# dcmctrl-hb-2-board_v1.net
KiCad netlist of a schematic drawn in EAGLE
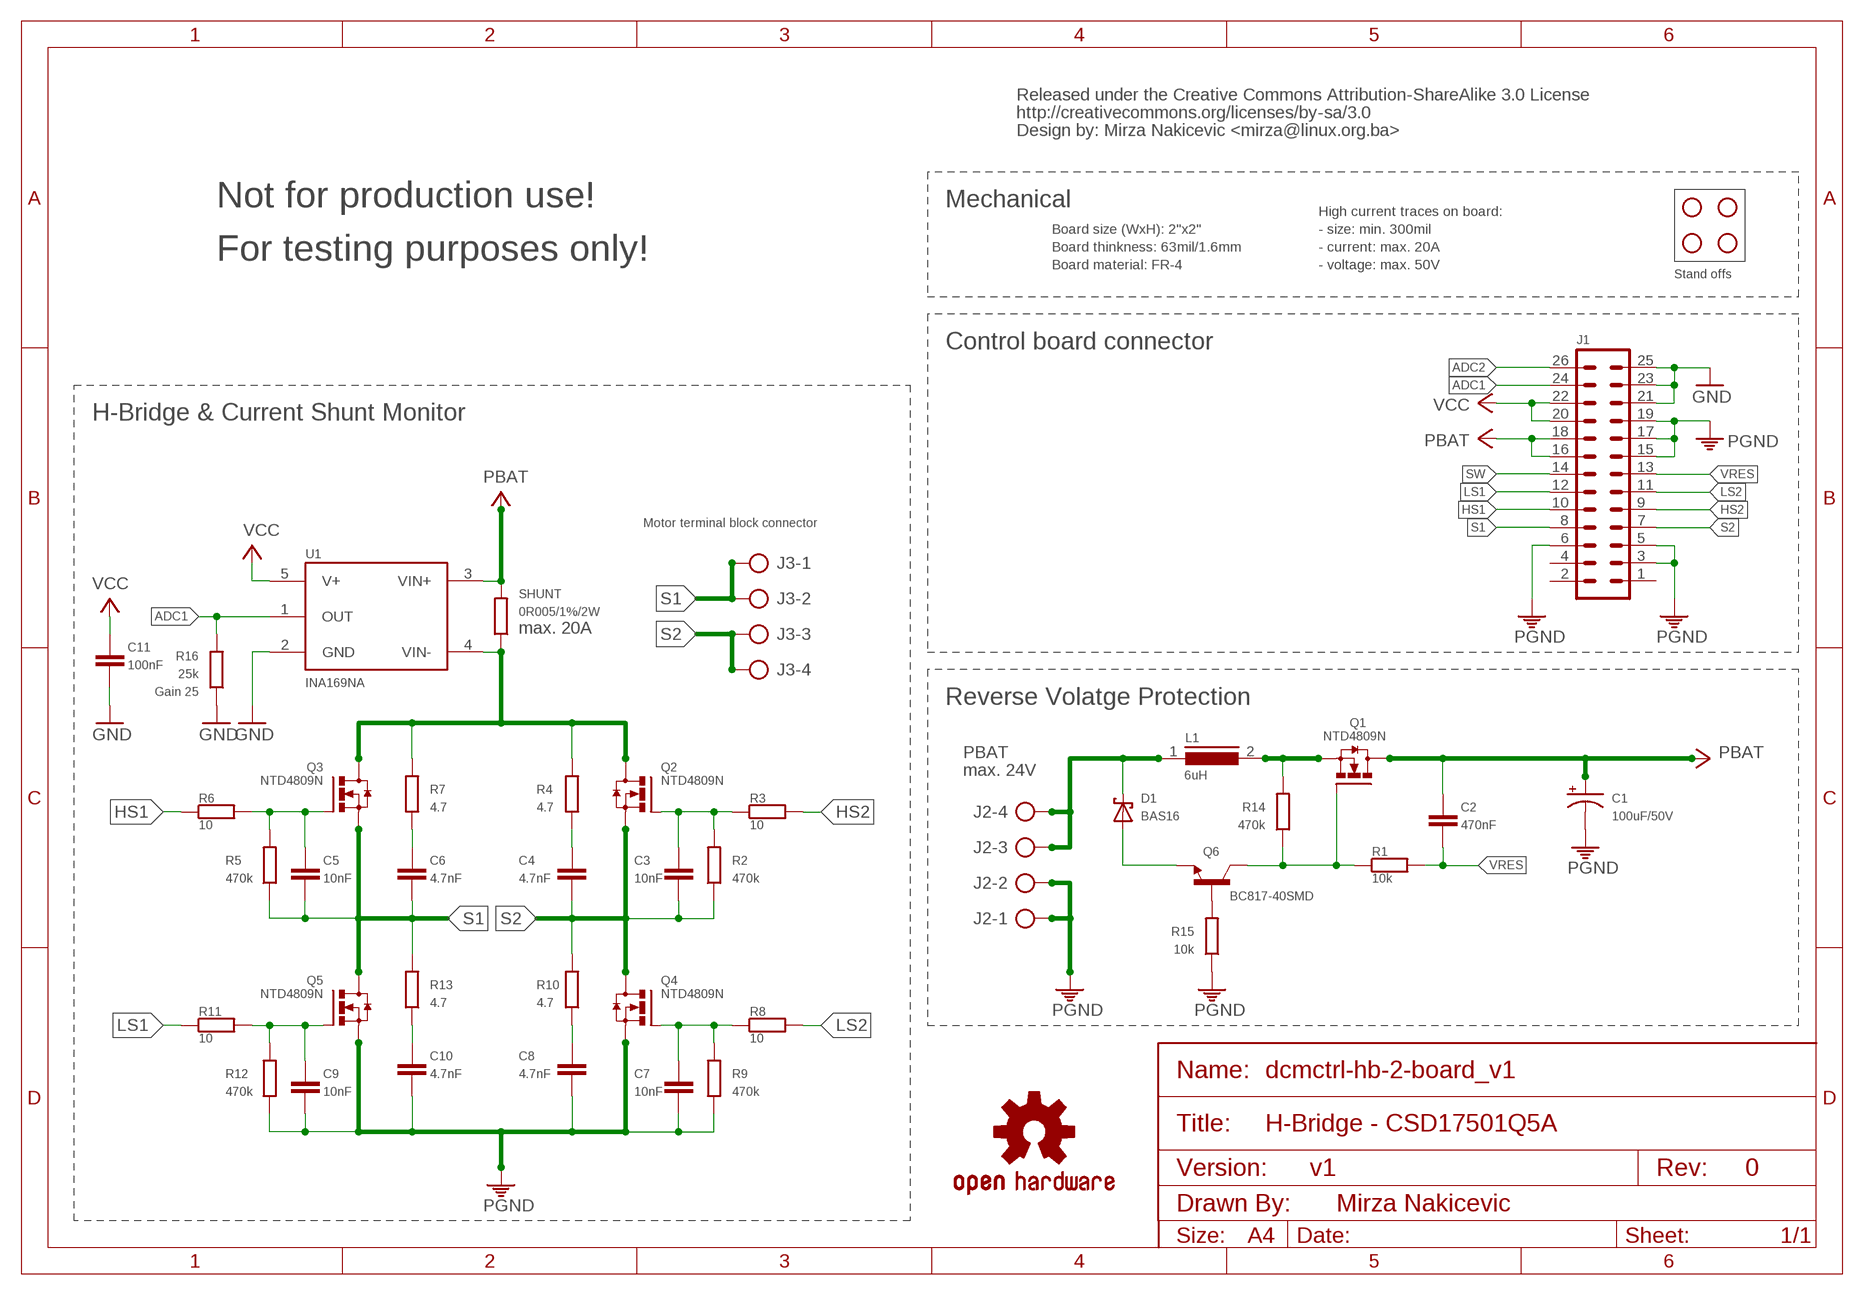
[diagram p0: schematic, sheet 1]

(export (version "E")
  (design (tool "Eeschema 10.0.6"))
  (components
    (comp (ref "C1")
      (value "100uF/50V")
      (footprint "eagle-import:E5-13")
      (libsource (lib "eagle-import") (part "CPOL-USE5-13"))
    )
    (comp (ref "C2")
      (value "470nF")
      (footprint "eagle-import:C0603")
      (libsource (lib "eagle-import") (part "C-0603"))
    )
    (comp (ref "C3")
      (value "10nF")
      (footprint "eagle-import:C0603")
      (libsource (lib "eagle-import") (part "C-0603"))
    )
    (comp (ref "C4")
      (value "4.7nF")
      (footprint "eagle-import:C0603")
      (libsource (lib "eagle-import") (part "C-0603"))
    )
    (comp (ref "C5")
      (value "10nF")
      (footprint "eagle-import:C0603")
      (libsource (lib "eagle-import") (part "C-0603"))
    )
    (comp (ref "C6")
      (value "4.7nF")
      (footprint "eagle-import:C0603")
      (libsource (lib "eagle-import") (part "C-0603"))
    )
    (comp (ref "C7")
      (value "10nF")
      (footprint "eagle-import:C0603")
      (libsource (lib "eagle-import") (part "C-0603"))
    )
    (comp (ref "C8")
      (value "4.7nF")
      (footprint "eagle-import:C0603")
      (libsource (lib "eagle-import") (part "C-0603"))
    )
    (comp (ref "C9")
      (value "10nF")
      (footprint "eagle-import:C0603")
      (libsource (lib "eagle-import") (part "C-0603"))
    )
    (comp (ref "C10")
      (value "4.7nF")
      (footprint "eagle-import:C0603")
      (libsource (lib "eagle-import") (part "C-0603"))
    )
    (comp (ref "C11")
      (value "100nF")
      (footprint "eagle-import:C0603")
      (libsource (lib "eagle-import") (part "C-0603"))
    )
    (comp (ref "D1")
      (value "BAS16")
      (footprint "eagle-import:SOT23")
      (libsource (lib "eagle-import") (part "BAS40"))
    )
    (comp (ref "J1")
      (value "MA13-2")
      (footprint "eagle-import:MA13-2")
      (libsource (lib "eagle-import") (part "MA13-2"))
    )
    (comp (ref "J2")
      (value "W237-4")
      (footprint "eagle-import:W237-4")
      (libsource (lib "eagle-import") (part "W237-4"))
    )
    (comp (ref "J3")
      (value "W237-4")
      (footprint "eagle-import:W237-4")
      (libsource (lib "eagle-import") (part "W237-4"))
    )
    (comp (ref "L1")
      (value "6uH")
      (footprint "eagle-import:DR127")
      (libsource (lib "eagle-import") (part "DR127"))
    )
    (comp (ref "Q1")
      (value "NTD4809N")
      (footprint "eagle-import:DPAK")
      (libsource (lib "eagle-import") (part "NTD4809N"))
    )
    (comp (ref "Q2")
      (value "NTD4809N")
      (footprint "eagle-import:DPAK")
      (libsource (lib "eagle-import") (part "NTD4809N"))
    )
    (comp (ref "Q3")
      (value "NTD4809N")
      (footprint "eagle-import:DPAK")
      (libsource (lib "eagle-import") (part "NTD4809N"))
    )
    (comp (ref "Q4")
      (value "NTD4809N")
      (footprint "eagle-import:DPAK")
      (libsource (lib "eagle-import") (part "NTD4809N"))
    )
    (comp (ref "Q5")
      (value "NTD4809N")
      (footprint "eagle-import:DPAK")
      (libsource (lib "eagle-import") (part "NTD4809N"))
    )
    (comp (ref "Q6")
      (value "BC817-40SMD")
      (footprint "eagle-import:SOT23-BEC")
      (libsource (lib "eagle-import") (part "BC817SMD-40"))
    )
    (comp (ref "R1")
      (value "10k")
      (footprint "eagle-import:R0603")
      (libsource (lib "eagle-import") (part "R-0603"))
    )
    (comp (ref "R2")
      (value "470k")
      (footprint "eagle-import:R0603")
      (libsource (lib "eagle-import") (part "R-0603"))
    )
    (comp (ref "R3")
      (value "10")
      (footprint "eagle-import:R0603")
      (libsource (lib "eagle-import") (part "R-0603"))
    )
    (comp (ref "R4")
      (value "4.7")
      (footprint "eagle-import:R0603")
      (libsource (lib "eagle-import") (part "R-0603"))
    )
    (comp (ref "R5")
      (value "470k")
      (footprint "eagle-import:R0603")
      (libsource (lib "eagle-import") (part "R-0603"))
    )
    (comp (ref "R6")
      (value "10")
      (footprint "eagle-import:R0603")
      (libsource (lib "eagle-import") (part "R-0603"))
    )
    (comp (ref "R7")
      (value "4.7")
      (footprint "eagle-import:R0603")
      (libsource (lib "eagle-import") (part "R-0603"))
    )
    (comp (ref "R8")
      (value "10")
      (footprint "eagle-import:R0603")
      (libsource (lib "eagle-import") (part "R-0603"))
    )
    (comp (ref "R9")
      (value "470k")
      (footprint "eagle-import:R0603")
      (libsource (lib "eagle-import") (part "R-0603"))
    )
    (comp (ref "R10")
      (value "4.7")
      (footprint "eagle-import:R0603")
      (libsource (lib "eagle-import") (part "R-0603"))
    )
    (comp (ref "R11")
      (value "10")
      (footprint "eagle-import:R0603")
      (libsource (lib "eagle-import") (part "R-0603"))
    )
    (comp (ref "R12")
      (value "470k")
      (footprint "eagle-import:R0603")
      (libsource (lib "eagle-import") (part "R-0603"))
    )
    (comp (ref "R13")
      (value "4.7")
      (footprint "eagle-import:R0603")
      (libsource (lib "eagle-import") (part "R-0603"))
    )
    (comp (ref "R14")
      (value "470k")
      (footprint "eagle-import:R0603")
      (libsource (lib "eagle-import") (part "R-0603"))
    )
    (comp (ref "R15")
      (value "10k")
      (footprint "eagle-import:R0603")
      (libsource (lib "eagle-import") (part "R-0603"))
    )
    (comp (ref "R16")
      (value "25k")
      (footprint "eagle-import:R0603")
      (libsource (lib "eagle-import") (part "R-0603"))
    )
    (comp (ref "SHUNT")
      (value "0R005/1%/2W")
      (footprint "eagle-import:R2512")
      (libsource (lib "eagle-import") (part "R-2512"))
    )
    (comp (ref "U$2")
      (value "STAND-OFF")
      (footprint "eagle-import:STAND-OFF")
      (libsource (lib "eagle-import") (part "STAND-OFF"))
    )
    (comp (ref "U$3")
      (value "STAND-OFF")
      (footprint "eagle-import:STAND-OFF")
      (libsource (lib "eagle-import") (part "STAND-OFF"))
    )
    (comp (ref "U$4")
      (value "STAND-OFF")
      (footprint "eagle-import:STAND-OFF")
      (libsource (lib "eagle-import") (part "STAND-OFF"))
    )
    (comp (ref "U$6")
      (value "STAND-OFF")
      (footprint "eagle-import:STAND-OFF")
      (libsource (lib "eagle-import") (part "STAND-OFF"))
    )
    (comp (ref "U$9")
      (value "CC-SA")
      (footprint "eagle-import:CC-SA")
      (libsource (lib "eagle-import") (part "CC-SA"))
    )
    (comp (ref "U$10")
      (value "OSHW-LOGOM")
      (footprint "eagle-import:OSHW-LOGO-M")
      (libsource (lib "eagle-import") (part "OSHW-LOGOM"))
    )
    (comp (ref "U1")
      (value "INA169NA")
      (footprint "eagle-import:SOT23-5")
      (libsource (lib "eagle-import") (part "INA169NA"))
    )
  )
  (nets
    (net (code "1") (name "ADC1") (class "Default")
      (node (ref "J1") (pin "24") (pinfunction "24_24") (pintype "passive"))
      (node (ref "R16") (pin "2") (pinfunction "2_2") (pintype "passive"))
      (node (ref "U1") (pin "1") (pinfunction "OUT_1") (pintype "output"))
    )
    (net (code "2") (name "ADC2") (class "Default")
      (node (ref "J1") (pin "26") (pinfunction "26_26") (pintype "passive"))
    )
    (net (code "3") (name "GND") (class "Default")
      (node (ref "C11") (pin "2") (pinfunction "2_2") (pintype "passive"))
      (node (ref "J1") (pin "21") (pinfunction "21_21") (pintype "passive"))
      (node (ref "J1") (pin "23") (pinfunction "23_23") (pintype "passive"))
      (node (ref "J1") (pin "25") (pinfunction "25_25") (pintype "passive"))
      (node (ref "R16") (pin "1") (pinfunction "1_1") (pintype "passive"))
      (node (ref "U1") (pin "2") (pinfunction "GND_2") (pintype "power_in"))
    )
    (net (code "4") (name "HS1") (class "Default")
      (node (ref "J1") (pin "10") (pinfunction "10_10") (pintype "passive"))
      (node (ref "R6") (pin "1") (pinfunction "1_1") (pintype "passive"))
    )
    (net (code "5") (name "HS2") (class "Default")
      (node (ref "J1") (pin "9") (pinfunction "9_9") (pintype "passive"))
      (node (ref "R3") (pin "2") (pinfunction "2_2") (pintype "passive"))
    )
    (net (code "6") (name "LS1") (class "Default")
      (node (ref "J1") (pin "12") (pinfunction "12_12") (pintype "passive"))
      (node (ref "R11") (pin "1") (pinfunction "1_1") (pintype "passive"))
    )
    (net (code "7") (name "LS2") (class "Default")
      (node (ref "J1") (pin "11") (pinfunction "11_11") (pintype "passive"))
      (node (ref "R8") (pin "2") (pinfunction "2_2") (pintype "passive"))
    )
    (net (code "8") (name "Net-(C4-Pad1)") (class "Default")
      (node (ref "C4") (pin "1") (pinfunction "1_1") (pintype "passive"))
      (node (ref "R4") (pin "1") (pinfunction "1_1") (pintype "passive"))
    )
    (net (code "9") (name "Net-(C6-Pad1)") (class "Default")
      (node (ref "C6") (pin "1") (pinfunction "1_1") (pintype "passive"))
      (node (ref "R7") (pin "1") (pinfunction "1_1") (pintype "passive"))
    )
    (net (code "10") (name "Net-(C8-Pad1)") (class "Default")
      (node (ref "C8") (pin "1") (pinfunction "1_1") (pintype "passive"))
      (node (ref "R10") (pin "1") (pinfunction "1_1") (pintype "passive"))
    )
    (net (code "11") (name "Net-(C10-Pad1)") (class "Default")
      (node (ref "C10") (pin "1") (pinfunction "1_1") (pintype "passive"))
      (node (ref "R13") (pin "1") (pinfunction "1_1") (pintype "passive"))
    )
    (net (code "12") (name "Net-(D1-A)") (class "Default")
      (node (ref "D1") (pin "1") (pinfunction "A_1") (pintype "passive"))
      (node (ref "Q6") (pin "E") (pinfunction "E_E") (pintype "passive"))
    )
    (net (code "13") (name "Net-(D1-C)") (class "Default")
      (node (ref "D1") (pin "3") (pinfunction "C_3") (pintype "passive"))
      (node (ref "J2") (pin "3") (pinfunction "KL_3") (pintype "passive"))
      (node (ref "J2") (pin "4") (pinfunction "KL_4") (pintype "passive"))
      (node (ref "L1") (pin "1") (pinfunction "1_1") (pintype "passive"))
    )
    (net (code "14") (name "Net-(Q1-G)") (class "Default")
      (node (ref "Q1") (pin "1") (pinfunction "G_1") (pintype "passive"))
      (node (ref "Q6") (pin "C") (pinfunction "C_C") (pintype "passive"))
      (node (ref "R1") (pin "1") (pinfunction "1_1") (pintype "passive"))
      (node (ref "R14") (pin "1") (pinfunction "1_1") (pintype "passive"))
    )
    (net (code "15") (name "Net-(Q1-S)") (class "Default")
      (node (ref "L1") (pin "2") (pinfunction "2_2") (pintype "passive"))
      (node (ref "Q1") (pin "3") (pinfunction "S_3") (pintype "passive"))
      (node (ref "R14") (pin "2") (pinfunction "2_2") (pintype "passive"))
    )
    (net (code "16") (name "Net-(Q2-D)") (class "Default")
      (node (ref "Q2") (pin "4") (pinfunction "D_4") (pintype "passive"))
      (node (ref "Q3") (pin "4") (pinfunction "D_4") (pintype "passive"))
      (node (ref "R4") (pin "2") (pinfunction "2_2") (pintype "passive"))
      (node (ref "R7") (pin "2") (pinfunction "2_2") (pintype "passive"))
      (node (ref "SHUNT") (pin "1") (pinfunction "1_1") (pintype "passive"))
      (node (ref "U1") (pin "4") (pinfunction "VIN-_4") (pintype "passive"))
    )
    (net (code "17") (name "Net-(Q2-G)") (class "Default")
      (node (ref "C3") (pin "1") (pinfunction "1_1") (pintype "passive"))
      (node (ref "Q2") (pin "1") (pinfunction "G_1") (pintype "passive"))
      (node (ref "R2") (pin "2") (pinfunction "2_2") (pintype "passive"))
      (node (ref "R3") (pin "1") (pinfunction "1_1") (pintype "passive"))
    )
    (net (code "18") (name "Net-(Q3-G)") (class "Default")
      (node (ref "C5") (pin "1") (pinfunction "1_1") (pintype "passive"))
      (node (ref "Q3") (pin "1") (pinfunction "G_1") (pintype "passive"))
      (node (ref "R5") (pin "2") (pinfunction "2_2") (pintype "passive"))
      (node (ref "R6") (pin "2") (pinfunction "2_2") (pintype "passive"))
    )
    (net (code "19") (name "Net-(Q4-G)") (class "Default")
      (node (ref "C7") (pin "1") (pinfunction "1_1") (pintype "passive"))
      (node (ref "Q4") (pin "1") (pinfunction "G_1") (pintype "passive"))
      (node (ref "R8") (pin "1") (pinfunction "1_1") (pintype "passive"))
      (node (ref "R9") (pin "2") (pinfunction "2_2") (pintype "passive"))
    )
    (net (code "20") (name "Net-(Q5-G)") (class "Default")
      (node (ref "C9") (pin "1") (pinfunction "1_1") (pintype "passive"))
      (node (ref "Q5") (pin "1") (pinfunction "G_1") (pintype "passive"))
      (node (ref "R11") (pin "2") (pinfunction "2_2") (pintype "passive"))
      (node (ref "R12") (pin "2") (pinfunction "2_2") (pintype "passive"))
    )
    (net (code "21") (name "Net-(Q6-PadB)") (class "Default")
      (node (ref "Q6") (pin "B") (pinfunction "B_B") (pintype "passive"))
      (node (ref "R15") (pin "2") (pinfunction "2_2") (pintype "passive"))
    )
    (net (code "22") (name "PBAT") (class "Default")
      (node (ref "C1") (pin "+") (pinfunction "+_+") (pintype "passive"))
      (node (ref "C2") (pin "1") (pinfunction "1_1") (pintype "passive"))
      (node (ref "J1") (pin "16") (pinfunction "16_16") (pintype "passive"))
      (node (ref "J1") (pin "18") (pinfunction "18_18") (pintype "passive"))
      (node (ref "Q1") (pin "4") (pinfunction "D_4") (pintype "passive"))
      (node (ref "SHUNT") (pin "2") (pinfunction "2_2") (pintype "passive"))
      (node (ref "U1") (pin "3") (pinfunction "VIN+_3") (pintype "passive"))
    )
    (net (code "23") (name "PGND") (class "Default")
      (node (ref "C1") (pin "-") (pinfunction "-_-") (pintype "passive"))
      (node (ref "C10") (pin "2") (pinfunction "2_2") (pintype "passive"))
      (node (ref "C7") (pin "2") (pinfunction "2_2") (pintype "passive"))
      (node (ref "C8") (pin "2") (pinfunction "2_2") (pintype "passive"))
      (node (ref "C9") (pin "2") (pinfunction "2_2") (pintype "passive"))
      (node (ref "J1") (pin "15") (pinfunction "15_15") (pintype "passive"))
      (node (ref "J1") (pin "17") (pinfunction "17_17") (pintype "passive"))
      (node (ref "J1") (pin "19") (pinfunction "19_19") (pintype "passive"))
      (node (ref "J1") (pin "3") (pinfunction "3_3") (pintype "passive"))
      (node (ref "J1") (pin "5") (pinfunction "5_5") (pintype "passive"))
      (node (ref "J1") (pin "6") (pinfunction "6_6") (pintype "passive"))
      (node (ref "J2") (pin "1") (pinfunction "KL_1") (pintype "passive"))
      (node (ref "J2") (pin "2") (pinfunction "KL_2") (pintype "passive"))
      (node (ref "Q4") (pin "3") (pinfunction "S_3") (pintype "passive"))
      (node (ref "Q5") (pin "3") (pinfunction "S_3") (pintype "passive"))
      (node (ref "R12") (pin "1") (pinfunction "1_1") (pintype "passive"))
      (node (ref "R15") (pin "1") (pinfunction "1_1") (pintype "passive"))
      (node (ref "R9") (pin "1") (pinfunction "1_1") (pintype "passive"))
    )
    (net (code "24") (name "S1") (class "Default")
      (node (ref "C5") (pin "2") (pinfunction "2_2") (pintype "passive"))
      (node (ref "C6") (pin "2") (pinfunction "2_2") (pintype "passive"))
      (node (ref "J1") (pin "8") (pinfunction "8_8") (pintype "passive"))
      (node (ref "J3") (pin "1") (pinfunction "KL_1") (pintype "passive"))
      (node (ref "J3") (pin "2") (pinfunction "KL_2") (pintype "passive"))
      (node (ref "Q3") (pin "3") (pinfunction "S_3") (pintype "passive"))
      (node (ref "Q5") (pin "4") (pinfunction "D_4") (pintype "passive"))
      (node (ref "R13") (pin "2") (pinfunction "2_2") (pintype "passive"))
      (node (ref "R5") (pin "1") (pinfunction "1_1") (pintype "passive"))
    )
    (net (code "25") (name "S2") (class "Default")
      (node (ref "C3") (pin "2") (pinfunction "2_2") (pintype "passive"))
      (node (ref "C4") (pin "2") (pinfunction "2_2") (pintype "passive"))
      (node (ref "J1") (pin "7") (pinfunction "7_7") (pintype "passive"))
      (node (ref "J3") (pin "3") (pinfunction "KL_3") (pintype "passive"))
      (node (ref "J3") (pin "4") (pinfunction "KL_4") (pintype "passive"))
      (node (ref "Q2") (pin "3") (pinfunction "S_3") (pintype "passive"))
      (node (ref "Q4") (pin "4") (pinfunction "D_4") (pintype "passive"))
      (node (ref "R10") (pin "2") (pinfunction "2_2") (pintype "passive"))
      (node (ref "R2") (pin "1") (pinfunction "1_1") (pintype "passive"))
    )
    (net (code "26") (name "SW") (class "Default")
      (node (ref "J1") (pin "14") (pinfunction "14_14") (pintype "passive"))
    )
    (net (code "27") (name "VCC") (class "Default")
      (node (ref "C11") (pin "1") (pinfunction "1_1") (pintype "passive"))
      (node (ref "J1") (pin "20") (pinfunction "20_20") (pintype "passive"))
      (node (ref "J1") (pin "22") (pinfunction "22_22") (pintype "passive"))
      (node (ref "U1") (pin "5") (pinfunction "V+_5") (pintype "power_in"))
    )
    (net (code "28") (name "VRES") (class "Default")
      (node (ref "C2") (pin "2") (pinfunction "2_2") (pintype "passive"))
      (node (ref "J1") (pin "13") (pinfunction "13_13") (pintype "passive"))
      (node (ref "R1") (pin "2") (pinfunction "2_2") (pintype "passive"))
    )
    (net (code "29") (name "unconnected-(J1-Pad1)") (class "Default")
      (node (ref "J1") (pin "1") (pinfunction "1_1") (pintype "passive"))
    )
    (net (code "30") (name "unconnected-(J1-Pad2)") (class "Default")
      (node (ref "J1") (pin "2") (pinfunction "2_2") (pintype "passive"))
    )
    (net (code "31") (name "unconnected-(J1-Pad4)") (class "Default")
      (node (ref "J1") (pin "4") (pinfunction "4_4") (pintype "passive"))
    )
  )
)
